# LT3652-MPPT-Battery-Charger.net
KiCad netlist of a schematic drawn in EAGLE
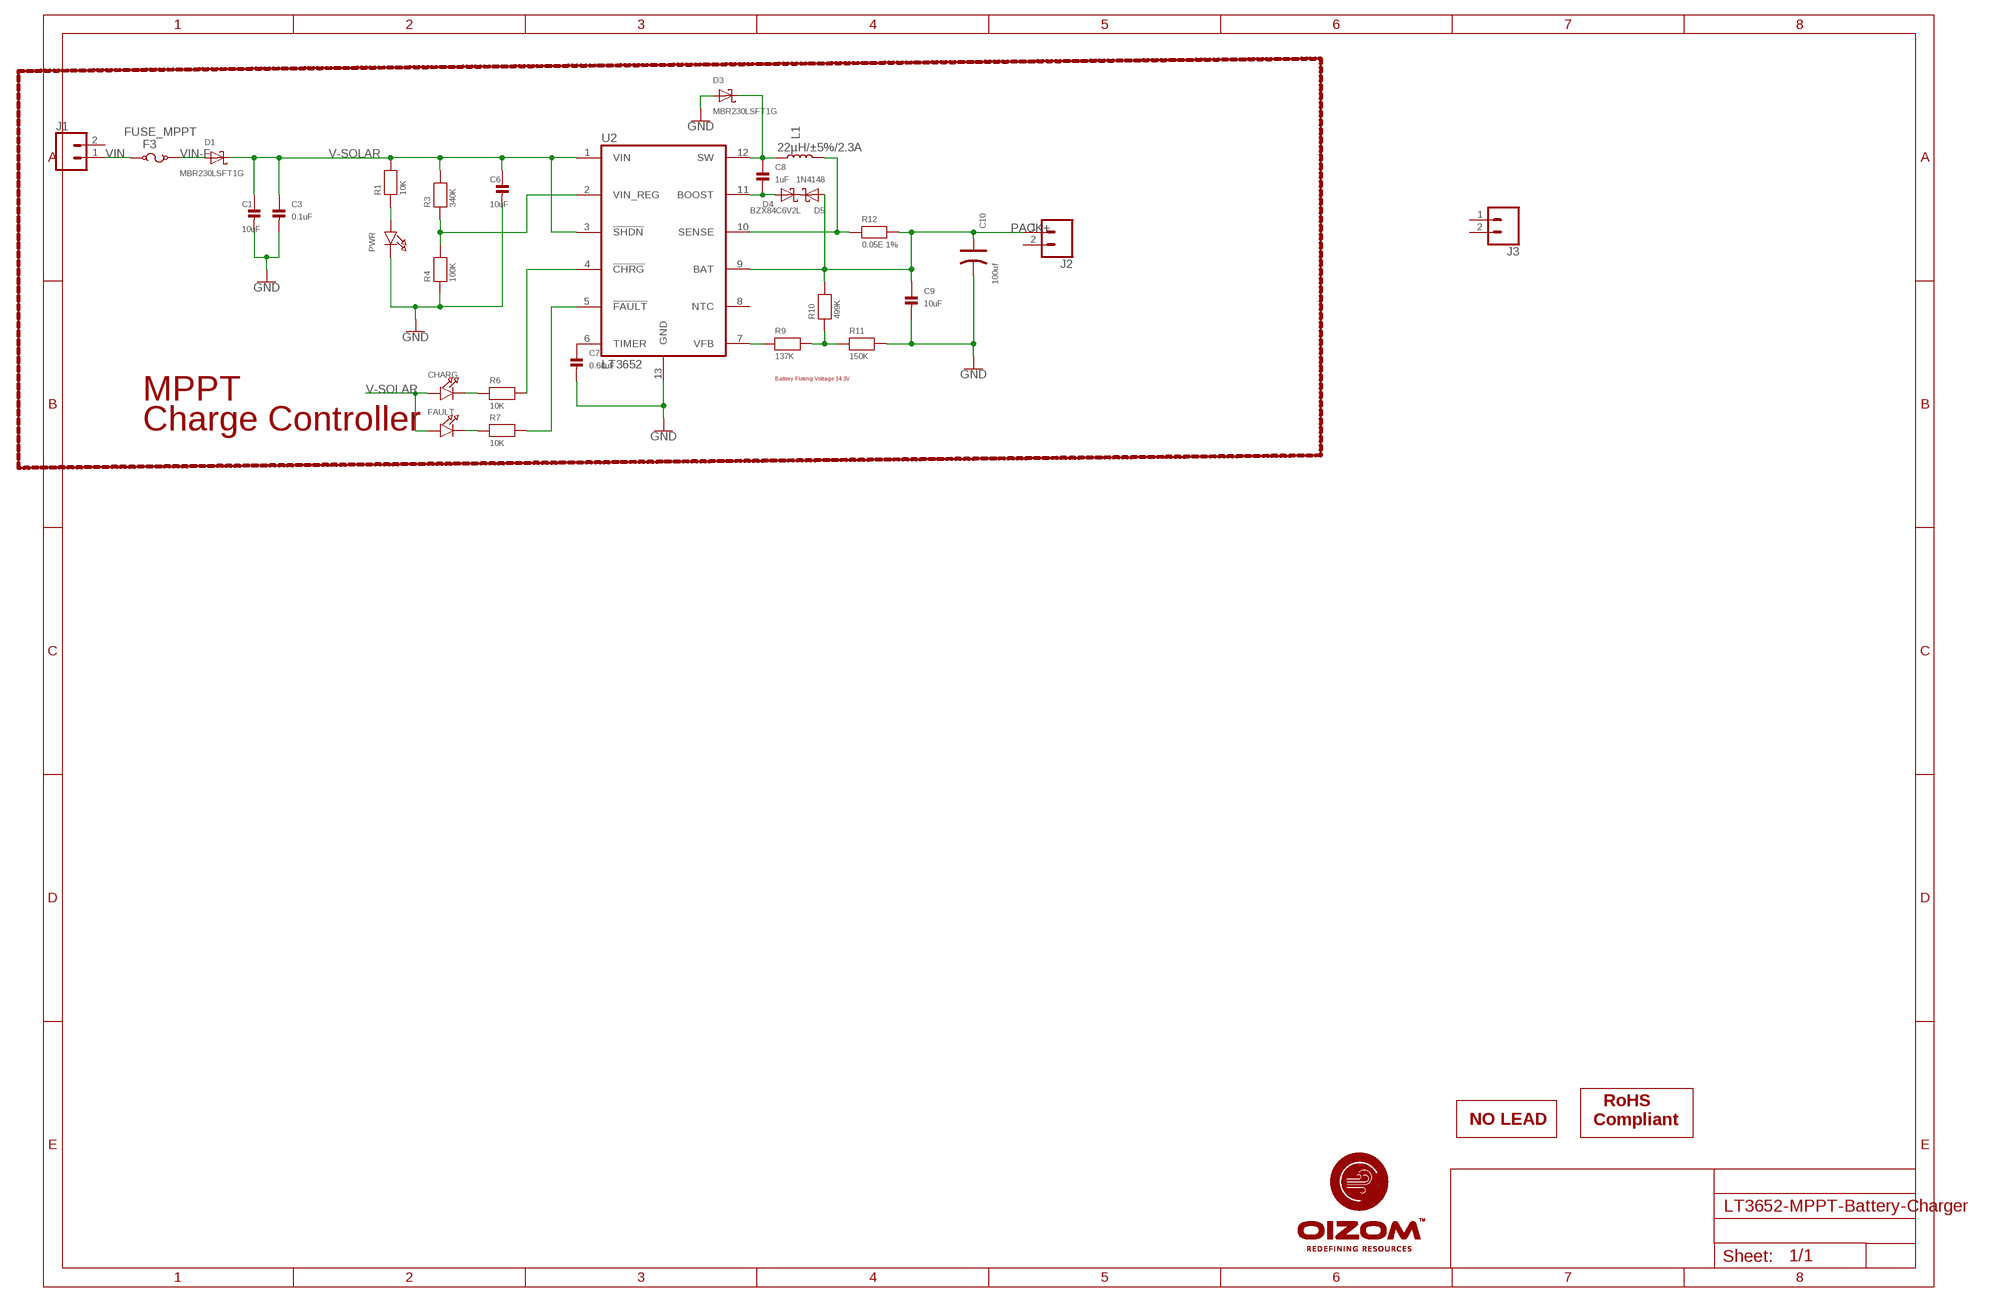
[diagram p0: schematic, sheet 1, part 2 of 2]

(export (version "E")
  (design (tool "Eeschema 10.0.6"))
  (components
    (comp (ref "C1")
      (value "10uF")
      (footprint "eagle-import:0805")
      (fields (field (name "MF") "MURATA") (field (name "MPN") "GRM21BR61E106KA73L"))
      (libsource (lib "eagle-import") (part "CAP_CERAMIC0805"))
    )
    (comp (ref "C3")
      (value "0.1uF")
      (footprint "eagle-import:0805")
      (fields (field (name "MF") "AVX") (field (name "MPN") "08055C104JAT2A"))
      (libsource (lib "eagle-import") (part "CAP_CERAMIC0805"))
    )
    (comp (ref "C6")
      (value "10uF")
      (footprint "eagle-import:0805")
      (fields (field (name "MF") "MURATA") (field (name "MPN") "GRM21BR61E106KA73L"))
      (libsource (lib "eagle-import") (part "CAP_CERAMIC0805"))
    )
    (comp (ref "C7")
      (value "0.68uF")
      (footprint "eagle-import:0805")
      (fields (field (name "MF") "YAGEO (PHYCOMP)") (field (name "MPN") "CC0805KKX7R6BB684"))
      (libsource (lib "eagle-import") (part "CAP_CERAMIC0805"))
    )
    (comp (ref "C8")
      (value "1uF")
      (footprint "eagle-import:0805")
      (fields (field (name "MF") "KEMET") (field (name "MPN") "C0805C105K3RACTU"))
      (libsource (lib "eagle-import") (part "CAP_CERAMIC0805"))
    )
    (comp (ref "C9")
      (value "10uF")
      (footprint "eagle-import:0805")
      (fields (field (name "MF") "MURATA") (field (name "MPN") "GRM21BR61E106KA73L"))
      (libsource (lib "eagle-import") (part "CAP_CERAMIC0805"))
    )
    (comp (ref "C10")
      (value "100uf")
      (footprint "eagle-import:AVX-C")
      (fields
        (field (name "MPN") "TAJC107K016RNJ")
        (field (name "MF") "AVX")
        (field (name "MPN_1") "TAJD107K016RNJ")
      )
      (libsource (lib "eagle-import") (part "TANTALUM-SMD-100UF-16V(AVX-C)"))
    )
    (comp (ref "CHARG")
      (value "LED0603_NOOUTLINE")
      (footprint "eagle-import:CHIPLED_0603_NOOUTLINE")
      (libsource (lib "eagle-import") (part "LED0603_NOOUTLINE"))
    )
    (comp (ref "D1")
      (value "MBR230LSFT1G")
      (footprint "eagle-import:SOD-123")
      (fields (field (name "MF") "ON SEMICONDUCTOR"))
      (libsource (lib "eagle-import") (part "DIODESOD-123"))
    )
    (comp (ref "D3")
      (value "MBR230LSFT1G")
      (footprint "eagle-import:SOD-123")
      (fields (field (name "MF") "ON SEMICONDUCTOR"))
      (libsource (lib "eagle-import") (part "DIODESOD-123"))
    )
    (comp (ref "D4")
      (value "BZX84C6V2L")
      (footprint "eagle-import:SOT23-R")
      (fields (field (name "MF") "ON SEMICONDUCTOR") (field (name "MPN") "BZX84C6V2LT1G"))
      (libsource (lib "eagle-import") (part "DIODESOT23_REFLOW"))
    )
    (comp (ref "D5")
      (value "1N4148")
      (footprint "eagle-import:SOD-323F")
      (fields (field (name "MF") "MULTICOMP") (field (name "MPN") "1N4148WS."))
      (libsource (lib "eagle-import") (part "DIODESOD-323F"))
    )
    (comp (ref "F3")
      (value "FUSE_MPPT")
      (footprint "eagle-import:FUSE_MPPT")
      (libsource (lib "eagle-import") (part "FUSE_MPPT"))
    )
    (comp (ref "FAULT")
      (value "LED0603_NOOUTLINE")
      (footprint "eagle-import:CHIPLED_0603_NOOUTLINE")
      (libsource (lib "eagle-import") (part "LED0603_NOOUTLINE"))
    )
    (comp (ref "J1")
      (value "CONN_025MM")
      (footprint "eagle-import:SCREWTERMINAL-5MM-2")
      (libsource (lib "eagle-import") (part "CONN_025MM"))
    )
    (comp (ref "J2")
      (value "CONN_025MM")
      (footprint "eagle-import:SCREWTERMINAL-5MM-2")
      (libsource (lib "eagle-import") (part "CONN_025MM"))
    )
    (comp (ref "J3")
      (value "CONN_025MM")
      (footprint "eagle-import:SCREWTERMINAL-5MM-2")
      (libsource (lib "eagle-import") (part "CONN_025MM"))
    )
    (comp (ref "L1")
      (value "22µH/±5%/2.3A")
      (footprint "eagle-import:SRN6045")
      (fields (field (name "MF") "BOURNS") (field (name "MPN") "SRN6045TA-100M"))
      (libsource (lib "eagle-import") (part "INDUCTOR-SRN6045-33UH"))
    )
    (comp (ref "PWR")
      (value "LED0603_NOOUTLINE")
      (footprint "eagle-import:CHIPLED_0603_NOOUTLINE")
      (libsource (lib "eagle-import") (part "LED0603_NOOUTLINE"))
    )
    (comp (ref "R1")
      (value "10K")
      (footprint "eagle-import:0805")
      (fields (field (name "MF") "YAGEO (PHYCOMP)") (field (name "MPN") "RC0805FR-0710KL"))
      (libsource (lib "eagle-import") (part "RESISTOR0805"))
    )
    (comp (ref "R3")
      (value "340K")
      (footprint "eagle-import:0805")
      (fields (field (name "MF") "PANASONIC ELECTRONIC COMPONENTS") (field (name "MPN") "ERJ6ENF3403V"))
      (libsource (lib "eagle-import") (part "RESISTOR0805"))
    )
    (comp (ref "R4")
      (value "100K")
      (footprint "eagle-import:0805")
      (fields (field (name "MF") "MULTICOMP") (field (name "MPN") "MCWR08X1003FTL"))
      (libsource (lib "eagle-import") (part "RESISTOR0805"))
    )
    (comp (ref "R6")
      (value "10K")
      (footprint "eagle-import:0805")
      (fields (field (name "MF") "YAGEO (PHYCOMP)") (field (name "MPN") "RC0805FR-0710KL"))
      (libsource (lib "eagle-import") (part "RESISTOR0805"))
    )
    (comp (ref "R7")
      (value "10K")
      (footprint "eagle-import:0805")
      (fields (field (name "MF") "YAGEO (PHYCOMP)") (field (name "MPN") "RC0805FR-0710KL"))
      (libsource (lib "eagle-import") (part "RESISTOR0805"))
    )
    (comp (ref "R9")
      (value "137K")
      (footprint "eagle-import:0805")
      (fields (field (name "MF") "PANASONIC ELECTRONIC COMPONENTS") (field (name "MPN") "ERJ6ENF1373V"))
      (libsource (lib "eagle-import") (part "RESISTOR0805"))
    )
    (comp (ref "R10")
      (value "499K")
      (footprint "eagle-import:0805")
      (fields (field (name "MF") "PANASONIC ELECTRONIC COMPONENTS") (field (name "MPN") "ERJ6ENF5103V"))
      (libsource (lib "eagle-import") (part "RESISTOR0805"))
    )
    (comp (ref "R11")
      (value "150K")
      (footprint "eagle-import:0805")
      (fields (field (name "MF") "PANASONIC ELECTRONIC COMPONENTS") (field (name "MPN") "ERJ6GEYJ154V"))
      (libsource (lib "eagle-import") (part "RESISTOR0805"))
    )
    (comp (ref "R12")
      (value "0.05E 1%")
      (footprint "eagle-import:0805")
      (fields (field (name "MF") "PANASONIC ELECTRONIC COMPONENTS") (field (name "MPN") "ERJ6BWFR050V"))
      (libsource (lib "eagle-import") (part "RESISTOR0805"))
    )
    (comp (ref "U$1")
      (value "NOPB_LOGO_SYM")
      (footprint "eagle-import:NOPB_LOGO_SYM")
      (libsource (lib "eagle-import") (part "NOPB_LOGO_SYM"))
    )
    (comp (ref "U$2")
      (value "ROHS_LOGO")
      (footprint "eagle-import:ROHS_LOGO_SYM")
      (libsource (lib "eagle-import") (part "ROHS_LOGO"))
    )
    (comp (ref "U2")
      (value "LT3652")
      (footprint "eagle-import:MSOP12-MSE")
      (fields (field (name "MF") "LINEAR TECHNOLOGY") (field (name "MPN") "LT3652EMSE#PBF"))
      (libsource (lib "eagle-import") (part "LT3652"))
    )
  )
  (nets
    (net (code "1") (name "/PACK+") (class "Default")
      (node (ref "C10") (pin "+") (pinfunction "+_+") (pintype "passive"))
      (node (ref "C9") (pin "1") (pinfunction "P$1_1") (pintype "passive"))
      (node (ref "D5") (pin "A") (pinfunction "A_A") (pintype "passive"))
      (node (ref "J2") (pin "1") (pinfunction "1_1") (pintype "passive"))
      (node (ref "R10") (pin "2") (pinfunction "2_2") (pintype "passive"))
      (node (ref "R12") (pin "2") (pinfunction "2_2") (pintype "passive"))
      (node (ref "U2") (pin "9") (pinfunction "BAT_9") (pintype "output"))
    )
    (net (code "2") (name "/V-SOLAR") (class "Default")
      (node (ref "C1") (pin "1") (pinfunction "P$1_1") (pintype "passive"))
      (node (ref "C3") (pin "1") (pinfunction "P$1_1") (pintype "passive"))
      (node (ref "C6") (pin "1") (pinfunction "P$1_1") (pintype "passive"))
      (node (ref "CHARG") (pin "A") (pinfunction "A_A") (pintype "passive"))
      (node (ref "D1") (pin "C") (pinfunction "C_C") (pintype "passive"))
      (node (ref "FAULT") (pin "A") (pinfunction "A_A") (pintype "passive"))
      (node (ref "R1") (pin "2") (pinfunction "2_2") (pintype "passive"))
      (node (ref "R3") (pin "2") (pinfunction "2_2") (pintype "passive"))
      (node (ref "U2") (pin "1") (pinfunction "VIN_1") (pintype "input"))
      (node (ref "U2") (pin "3") (pinfunction "~{SHDN}_3") (pintype "input"))
    )
    (net (code "3") (name "/VIN") (class "Default")
      (node (ref "F3") (pin "1") (pinfunction "1_1") (pintype "passive"))
      (node (ref "J1") (pin "1") (pinfunction "1_1") (pintype "passive"))
    )
    (net (code "4") (name "/VIN-F") (class "Default")
      (node (ref "D1") (pin "A") (pinfunction "A_A") (pintype "passive"))
      (node (ref "F3") (pin "2") (pinfunction "2_2") (pintype "passive"))
    )
    (net (code "5") (name "GND") (class "Default")
      (node (ref "C1") (pin "2") (pinfunction "P$2_2") (pintype "passive"))
      (node (ref "C10") (pin "-") (pinfunction "-_-") (pintype "passive"))
      (node (ref "C3") (pin "2") (pinfunction "P$2_2") (pintype "passive"))
      (node (ref "C6") (pin "2") (pinfunction "P$2_2") (pintype "passive"))
      (node (ref "C7") (pin "2") (pinfunction "P$2_2") (pintype "passive"))
      (node (ref "C9") (pin "2") (pinfunction "P$2_2") (pintype "passive"))
      (node (ref "D3") (pin "A") (pinfunction "A_A") (pintype "passive"))
      (node (ref "PWR") (pin "C") (pinfunction "C_C") (pintype "passive"))
      (node (ref "R11") (pin "2") (pinfunction "2_2") (pintype "passive"))
      (node (ref "R4") (pin "1") (pinfunction "1_1") (pintype "passive"))
      (node (ref "U2") (pin "13") (pinfunction "GND_13") (pintype "open_collector"))
    )
    (net (code "6") (name "Net-(C7-P$1)") (class "Default")
      (node (ref "C7") (pin "1") (pinfunction "P$1_1") (pintype "passive"))
      (node (ref "U2") (pin "6") (pinfunction "TIMER_6") (pintype "input"))
    )
    (net (code "7") (name "Net-(C8-P$1)") (class "Default")
      (node (ref "C8") (pin "1") (pinfunction "P$1_1") (pintype "passive"))
      (node (ref "D3") (pin "C") (pinfunction "C_C") (pintype "passive"))
      (node (ref "L1") (pin "1") (pinfunction "1_1") (pintype "passive"))
      (node (ref "U2") (pin "12") (pinfunction "SW_12") (pintype "input"))
    )
    (net (code "8") (name "Net-(C8-P$2)") (class "Default")
      (node (ref "C8") (pin "2") (pinfunction "P$2_2") (pintype "passive"))
      (node (ref "D4") (pin "1") (pinfunction "A_1") (pintype "passive"))
      (node (ref "U2") (pin "11") (pinfunction "BOOST_11") (pintype "input"))
    )
    (net (code "9") (name "Net-(CHARG-PadC)") (class "Default")
      (node (ref "CHARG") (pin "C") (pinfunction "C_C") (pintype "passive"))
      (node (ref "R6") (pin "1") (pinfunction "1_1") (pintype "passive"))
    )
    (net (code "10") (name "Net-(D4-C)") (class "Default")
      (node (ref "D4") (pin "3") (pinfunction "C_3") (pintype "passive"))
      (node (ref "D5") (pin "C") (pinfunction "C_C") (pintype "passive"))
    )
    (net (code "11") (name "Net-(FAULT-PadC)") (class "Default")
      (node (ref "FAULT") (pin "C") (pinfunction "C_C") (pintype "passive"))
      (node (ref "R7") (pin "1") (pinfunction "1_1") (pintype "passive"))
    )
    (net (code "12") (name "Net-(PWR-PadA)") (class "Default")
      (node (ref "PWR") (pin "A") (pinfunction "A_A") (pintype "passive"))
      (node (ref "R1") (pin "1") (pinfunction "1_1") (pintype "passive"))
    )
    (net (code "13") (name "Net-(R10-Pad1)") (class "Default")
      (node (ref "R10") (pin "1") (pinfunction "1_1") (pintype "passive"))
      (node (ref "R11") (pin "1") (pinfunction "1_1") (pintype "passive"))
      (node (ref "R9") (pin "2") (pinfunction "2_2") (pintype "passive"))
    )
    (net (code "14") (name "Net-(U2-SENSE)") (class "Default")
      (node (ref "L1") (pin "2") (pinfunction "2_2") (pintype "passive"))
      (node (ref "R12") (pin "1") (pinfunction "1_1") (pintype "passive"))
      (node (ref "U2") (pin "10") (pinfunction "SENSE_10") (pintype "input"))
    )
    (net (code "15") (name "Net-(U2-VFB)") (class "Default")
      (node (ref "R9") (pin "1") (pinfunction "1_1") (pintype "passive"))
      (node (ref "U2") (pin "7") (pinfunction "VFB_7") (pintype "input"))
    )
    (net (code "16") (name "Net-(U2-VIN_REG)") (class "Default")
      (node (ref "R3") (pin "1") (pinfunction "1_1") (pintype "passive"))
      (node (ref "R4") (pin "2") (pinfunction "2_2") (pintype "passive"))
      (node (ref "U2") (pin "2") (pinfunction "VIN_REG_2") (pintype "input"))
    )
    (net (code "17") (name "Net-(U2-~{CHRG})") (class "Default")
      (node (ref "R6") (pin "2") (pinfunction "2_2") (pintype "passive"))
      (node (ref "U2") (pin "4") (pinfunction "~{CHRG}_4") (pintype "open_collector"))
    )
    (net (code "18") (name "Net-(U2-~{FAULT})") (class "Default")
      (node (ref "R7") (pin "2") (pinfunction "2_2") (pintype "passive"))
      (node (ref "U2") (pin "5") (pinfunction "~{FAULT}_5") (pintype "open_collector"))
    )
    (net (code "19") (name "unconnected-(J1-Pad2)") (class "Default")
      (node (ref "J1") (pin "2") (pinfunction "2_2") (pintype "passive"))
    )
    (net (code "20") (name "unconnected-(J2-Pad2)") (class "Default")
      (node (ref "J2") (pin "2") (pinfunction "2_2") (pintype "passive"))
    )
    (net (code "21") (name "unconnected-(J3-Pad1)") (class "Default")
      (node (ref "J3") (pin "1") (pinfunction "1_1") (pintype "passive"))
    )
    (net (code "22") (name "unconnected-(J3-Pad2)") (class "Default")
      (node (ref "J3") (pin "2") (pinfunction "2_2") (pintype "passive"))
    )
    (net (code "23") (name "unconnected-(U2-NTC-Pad8)") (class "Default")
      (node (ref "U2") (pin "8") (pinfunction "NTC_8") (pintype "input"))
    )
  )
)
